# MCU_pinout.net
KiCad netlist of a schematic drawn in Altium Designer
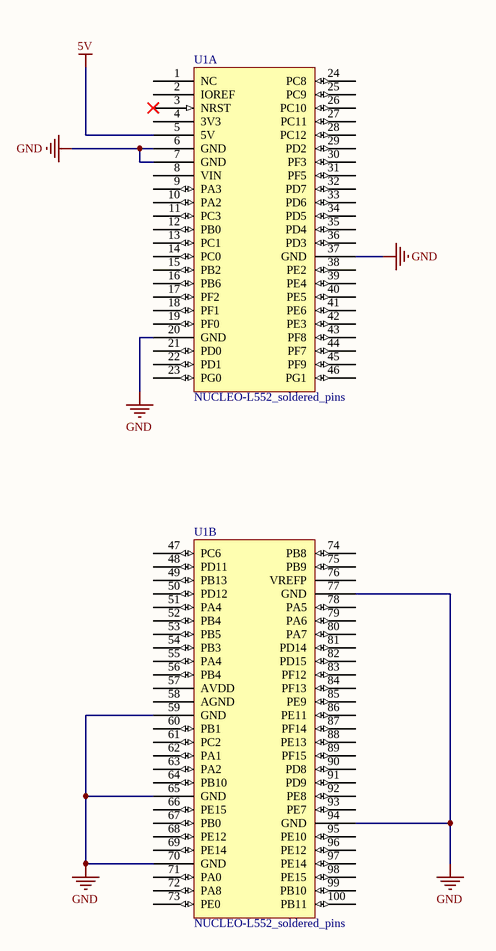
[diagram p0: MCU_pinout.SchDoc]

(export (version "E")
  (design (tool "Eeschema 10.0.6"))
  (components
    (comp (ref "U1")
      (value "NUCLEO-L552_soldered_pins")
      (footprint "FP_NUCLEO-144 inner connector")
      (libsource (lib "hallglib") (part "NUCLEO-L552_inner"))
    )
  )
  (nets
    (net (code "1") (name "5V") (class "Default")
      (node (ref "U1") (pin "5") (pinfunction "5V_5") (pintype "power_in"))
    )
    (net (code "2") (name "GND") (class "Default")
      (node (ref "U1") (pin "20") (pinfunction "GND_20") (pintype "power_in"))
      (node (ref "U1") (pin "37") (pinfunction "GND_37") (pintype "power_in"))
      (node (ref "U1") (pin "59") (pinfunction "GND_59") (pintype "power_in"))
      (node (ref "U1") (pin "6") (pinfunction "GND_6") (pintype "power_in"))
      (node (ref "U1") (pin "65") (pinfunction "GND_65") (pintype "power_in"))
      (node (ref "U1") (pin "7") (pinfunction "GND_7") (pintype "power_in"))
      (node (ref "U1") (pin "70") (pinfunction "GND_70") (pintype "power_in"))
      (node (ref "U1") (pin "77") (pinfunction "GND_77") (pintype "power_in"))
      (node (ref "U1") (pin "94") (pinfunction "GND_94") (pintype "power_in"))
    )
    (net (code "3") (name "unconnected-(U1A-3V3-Pad4)") (class "Default")
      (node (ref "U1") (pin "4") (pinfunction "3V3_4") (pintype "power_in"))
    )
    (net (code "4") (name "unconnected-(U1A-IOREF-Pad2)") (class "Default")
      (node (ref "U1") (pin "2") (pinfunction "IOREF_2") (pintype "power_in"))
    )
    (net (code "5") (name "unconnected-(U1A-NC-Pad1)") (class "Default")
      (node (ref "U1") (pin "1") (pinfunction "NC_1") (pintype "passive"))
    )
    (net (code "6") (name "unconnected-(U1A-NRST-Pad3)") (class "Default")
      (node (ref "U1") (pin "3") (pinfunction "NRST_3") (pintype "input+no_connect"))
    )
    (net (code "7") (name "unconnected-(U1A-PA2-Pad10)") (class "Default")
      (node (ref "U1") (pin "10") (pinfunction "PA2_10") (pintype "bidirectional"))
    )
    (net (code "8") (name "unconnected-(U1A-PA3-Pad9)") (class "Default")
      (node (ref "U1") (pin "9") (pinfunction "PA3_9") (pintype "bidirectional"))
    )
    (net (code "9") (name "unconnected-(U1A-PB0-Pad12)") (class "Default")
      (node (ref "U1") (pin "12") (pinfunction "PB0_12") (pintype "bidirectional"))
    )
    (net (code "10") (name "unconnected-(U1A-PB2-Pad15)") (class "Default")
      (node (ref "U1") (pin "15") (pinfunction "PB2_15") (pintype "bidirectional"))
    )
    (net (code "11") (name "unconnected-(U1A-PB6-Pad16)") (class "Default")
      (node (ref "U1") (pin "16") (pinfunction "PB6_16") (pintype "bidirectional"))
    )
    (net (code "12") (name "unconnected-(U1A-PC0-Pad14)") (class "Default")
      (node (ref "U1") (pin "14") (pinfunction "PC0_14") (pintype "bidirectional"))
    )
    (net (code "13") (name "unconnected-(U1A-PC1-Pad13)") (class "Default")
      (node (ref "U1") (pin "13") (pinfunction "PC1_13") (pintype "bidirectional"))
    )
    (net (code "14") (name "unconnected-(U1A-PC3-Pad11)") (class "Default")
      (node (ref "U1") (pin "11") (pinfunction "PC3_11") (pintype "bidirectional"))
    )
    (net (code "15") (name "unconnected-(U1A-PC8-Pad24)") (class "Default")
      (node (ref "U1") (pin "24") (pinfunction "PC8_24") (pintype "bidirectional"))
    )
    (net (code "16") (name "unconnected-(U1A-PC9-Pad25)") (class "Default")
      (node (ref "U1") (pin "25") (pinfunction "PC9_25") (pintype "bidirectional"))
    )
    (net (code "17") (name "unconnected-(U1A-PC10-Pad26)") (class "Default")
      (node (ref "U1") (pin "26") (pinfunction "PC10_26") (pintype "bidirectional"))
    )
    (net (code "18") (name "unconnected-(U1A-PC11-Pad27)") (class "Default")
      (node (ref "U1") (pin "27") (pinfunction "PC11_27") (pintype "bidirectional"))
    )
    (net (code "19") (name "unconnected-(U1A-PC12-Pad28)") (class "Default")
      (node (ref "U1") (pin "28") (pinfunction "PC12_28") (pintype "bidirectional"))
    )
    (net (code "20") (name "unconnected-(U1A-PD0-Pad21)") (class "Default")
      (node (ref "U1") (pin "21") (pinfunction "PD0_21") (pintype "bidirectional"))
    )
    (net (code "21") (name "unconnected-(U1A-PD1-Pad22)") (class "Default")
      (node (ref "U1") (pin "22") (pinfunction "PD1_22") (pintype "bidirectional"))
    )
    (net (code "22") (name "unconnected-(U1A-PD2-Pad29)") (class "Default")
      (node (ref "U1") (pin "29") (pinfunction "PD2_29") (pintype "bidirectional"))
    )
    (net (code "23") (name "unconnected-(U1A-PD3-Pad36)") (class "Default")
      (node (ref "U1") (pin "36") (pinfunction "PD3_36") (pintype "bidirectional"))
    )
    (net (code "24") (name "unconnected-(U1A-PD4-Pad35)") (class "Default")
      (node (ref "U1") (pin "35") (pinfunction "PD4_35") (pintype "bidirectional"))
    )
    (net (code "25") (name "unconnected-(U1A-PD5-Pad34)") (class "Default")
      (node (ref "U1") (pin "34") (pinfunction "PD5_34") (pintype "bidirectional"))
    )
    (net (code "26") (name "unconnected-(U1A-PD6-Pad33)") (class "Default")
      (node (ref "U1") (pin "33") (pinfunction "PD6_33") (pintype "bidirectional"))
    )
    (net (code "27") (name "unconnected-(U1A-PD7-Pad32)") (class "Default")
      (node (ref "U1") (pin "32") (pinfunction "PD7_32") (pintype "bidirectional"))
    )
    (net (code "28") (name "unconnected-(U1A-PE2-Pad38)") (class "Default")
      (node (ref "U1") (pin "38") (pinfunction "PE2_38") (pintype "bidirectional"))
    )
    (net (code "29") (name "unconnected-(U1A-PE3-Pad42)") (class "Default")
      (node (ref "U1") (pin "42") (pinfunction "PE3_42") (pintype "bidirectional"))
    )
    (net (code "30") (name "unconnected-(U1A-PE4-Pad39)") (class "Default")
      (node (ref "U1") (pin "39") (pinfunction "PE4_39") (pintype "bidirectional"))
    )
    (net (code "31") (name "unconnected-(U1A-PE5-Pad40)") (class "Default")
      (node (ref "U1") (pin "40") (pinfunction "PE5_40") (pintype "bidirectional"))
    )
    (net (code "32") (name "unconnected-(U1A-PE6-Pad41)") (class "Default")
      (node (ref "U1") (pin "41") (pinfunction "PE6_41") (pintype "bidirectional"))
    )
    (net (code "33") (name "unconnected-(U1A-PF0-Pad19)") (class "Default")
      (node (ref "U1") (pin "19") (pinfunction "PF0_19") (pintype "bidirectional"))
    )
    (net (code "34") (name "unconnected-(U1A-PF1-Pad18)") (class "Default")
      (node (ref "U1") (pin "18") (pinfunction "PF1_18") (pintype "bidirectional"))
    )
    (net (code "35") (name "unconnected-(U1A-PF2-Pad17)") (class "Default")
      (node (ref "U1") (pin "17") (pinfunction "PF2_17") (pintype "bidirectional"))
    )
    (net (code "36") (name "unconnected-(U1A-PF3-Pad30)") (class "Default")
      (node (ref "U1") (pin "30") (pinfunction "PF3_30") (pintype "bidirectional"))
    )
    (net (code "37") (name "unconnected-(U1A-PF5-Pad31)") (class "Default")
      (node (ref "U1") (pin "31") (pinfunction "PF5_31") (pintype "bidirectional"))
    )
    (net (code "38") (name "unconnected-(U1A-PF7-Pad44)") (class "Default")
      (node (ref "U1") (pin "44") (pinfunction "PF7_44") (pintype "bidirectional"))
    )
    (net (code "39") (name "unconnected-(U1A-PF8-Pad43)") (class "Default")
      (node (ref "U1") (pin "43") (pinfunction "PF8_43") (pintype "bidirectional"))
    )
    (net (code "40") (name "unconnected-(U1A-PF9-Pad45)") (class "Default")
      (node (ref "U1") (pin "45") (pinfunction "PF9_45") (pintype "bidirectional"))
    )
    (net (code "41") (name "unconnected-(U1A-PG0-Pad23)") (class "Default")
      (node (ref "U1") (pin "23") (pinfunction "PG0_23") (pintype "bidirectional"))
    )
    (net (code "42") (name "unconnected-(U1A-PG1-Pad46)") (class "Default")
      (node (ref "U1") (pin "46") (pinfunction "PG1_46") (pintype "bidirectional"))
    )
    (net (code "43") (name "unconnected-(U1A-VIN-Pad8)") (class "Default")
      (node (ref "U1") (pin "8") (pinfunction "VIN_8") (pintype "power_in"))
    )
    (net (code "44") (name "unconnected-(U1B-AGND-Pad58)") (class "Default")
      (node (ref "U1") (pin "58") (pinfunction "AGND_58") (pintype "power_in"))
    )
    (net (code "45") (name "unconnected-(U1B-AVDD-Pad57)") (class "Default")
      (node (ref "U1") (pin "57") (pinfunction "AVDD_57") (pintype "power_in"))
    )
    (net (code "46") (name "unconnected-(U1B-PA0-Pad71)") (class "Default")
      (node (ref "U1") (pin "71") (pinfunction "PA0_71") (pintype "bidirectional"))
    )
    (net (code "47") (name "unconnected-(U1B-PA1-Pad62)") (class "Default")
      (node (ref "U1") (pin "62") (pinfunction "PA1_62") (pintype "bidirectional"))
    )
    (net (code "48") (name "unconnected-(U1B-PA2-Pad63)") (class "Default")
      (node (ref "U1") (pin "63") (pinfunction "PA2_63") (pintype "bidirectional"))
    )
    (net (code "49") (name "unconnected-(U1B-PA4-Pad51)") (class "Default")
      (node (ref "U1") (pin "51") (pinfunction "PA4_51") (pintype "bidirectional"))
    )
    (net (code "50") (name "unconnected-(U1B-PA4-Pad55)") (class "Default")
      (node (ref "U1") (pin "55") (pinfunction "PA4_55") (pintype "bidirectional"))
    )
    (net (code "51") (name "unconnected-(U1B-PA5-Pad78)") (class "Default")
      (node (ref "U1") (pin "78") (pinfunction "PA5_78") (pintype "bidirectional"))
    )
    (net (code "52") (name "unconnected-(U1B-PA6-Pad79)") (class "Default")
      (node (ref "U1") (pin "79") (pinfunction "PA6_79") (pintype "bidirectional"))
    )
    (net (code "53") (name "unconnected-(U1B-PA7-Pad80)") (class "Default")
      (node (ref "U1") (pin "80") (pinfunction "PA7_80") (pintype "bidirectional"))
    )
    (net (code "54") (name "unconnected-(U1B-PA8-Pad72)") (class "Default")
      (node (ref "U1") (pin "72") (pinfunction "PA8_72") (pintype "bidirectional"))
    )
    (net (code "55") (name "unconnected-(U1B-PB0-Pad67)") (class "Default")
      (node (ref "U1") (pin "67") (pinfunction "PB0_67") (pintype "bidirectional"))
    )
    (net (code "56") (name "unconnected-(U1B-PB1-Pad60)") (class "Default")
      (node (ref "U1") (pin "60") (pinfunction "PB1_60") (pintype "bidirectional"))
    )
    (net (code "57") (name "unconnected-(U1B-PB3-Pad54)") (class "Default")
      (node (ref "U1") (pin "54") (pinfunction "PB3_54") (pintype "bidirectional"))
    )
    (net (code "58") (name "unconnected-(U1B-PB4-Pad52)") (class "Default")
      (node (ref "U1") (pin "52") (pinfunction "PB4_52") (pintype "bidirectional"))
    )
    (net (code "59") (name "unconnected-(U1B-PB4-Pad56)") (class "Default")
      (node (ref "U1") (pin "56") (pinfunction "PB4_56") (pintype "bidirectional"))
    )
    (net (code "60") (name "unconnected-(U1B-PB5-Pad53)") (class "Default")
      (node (ref "U1") (pin "53") (pinfunction "PB5_53") (pintype "bidirectional"))
    )
    (net (code "61") (name "unconnected-(U1B-PB8-Pad74)") (class "Default")
      (node (ref "U1") (pin "74") (pinfunction "PB8_74") (pintype "bidirectional"))
    )
    (net (code "62") (name "unconnected-(U1B-PB9-Pad75)") (class "Default")
      (node (ref "U1") (pin "75") (pinfunction "PB9_75") (pintype "bidirectional"))
    )
    (net (code "63") (name "unconnected-(U1B-PB10-Pad64)") (class "Default")
      (node (ref "U1") (pin "64") (pinfunction "PB10_64") (pintype "bidirectional"))
    )
    (net (code "64") (name "unconnected-(U1B-PB10-Pad99)") (class "Default")
      (node (ref "U1") (pin "99") (pinfunction "PB10_99") (pintype "bidirectional"))
    )
    (net (code "65") (name "unconnected-(U1B-PB11-Pad100)") (class "Default")
      (node (ref "U1") (pin "100") (pinfunction "PB11_100") (pintype "bidirectional"))
    )
    (net (code "66") (name "unconnected-(U1B-PB13-Pad49)") (class "Default")
      (node (ref "U1") (pin "49") (pinfunction "PB13_49") (pintype "bidirectional"))
    )
    (net (code "67") (name "unconnected-(U1B-PC2-Pad61)") (class "Default")
      (node (ref "U1") (pin "61") (pinfunction "PC2_61") (pintype "bidirectional"))
    )
    (net (code "68") (name "unconnected-(U1B-PC6-Pad47)") (class "Default")
      (node (ref "U1") (pin "47") (pinfunction "PC6_47") (pintype "bidirectional"))
    )
    (net (code "69") (name "unconnected-(U1B-PD8-Pad90)") (class "Default")
      (node (ref "U1") (pin "90") (pinfunction "PD8_90") (pintype "bidirectional"))
    )
    (net (code "70") (name "unconnected-(U1B-PD9-Pad91)") (class "Default")
      (node (ref "U1") (pin "91") (pinfunction "PD9_91") (pintype "bidirectional"))
    )
    (net (code "71") (name "unconnected-(U1B-PD11-Pad48)") (class "Default")
      (node (ref "U1") (pin "48") (pinfunction "PD11_48") (pintype "bidirectional"))
    )
    (net (code "72") (name "unconnected-(U1B-PD12-Pad50)") (class "Default")
      (node (ref "U1") (pin "50") (pinfunction "PD12_50") (pintype "bidirectional"))
    )
    (net (code "73") (name "unconnected-(U1B-PD14-Pad81)") (class "Default")
      (node (ref "U1") (pin "81") (pinfunction "PD14_81") (pintype "bidirectional"))
    )
    (net (code "74") (name "unconnected-(U1B-PD15-Pad82)") (class "Default")
      (node (ref "U1") (pin "82") (pinfunction "PD15_82") (pintype "bidirectional"))
    )
    (net (code "75") (name "unconnected-(U1B-PE0-Pad73)") (class "Default")
      (node (ref "U1") (pin "73") (pinfunction "PE0_73") (pintype "bidirectional"))
    )
    (net (code "76") (name "unconnected-(U1B-PE7-Pad93)") (class "Default")
      (node (ref "U1") (pin "93") (pinfunction "PE7_93") (pintype "bidirectional"))
    )
    (net (code "77") (name "unconnected-(U1B-PE8-Pad92)") (class "Default")
      (node (ref "U1") (pin "92") (pinfunction "PE8_92") (pintype "bidirectional"))
    )
    (net (code "78") (name "unconnected-(U1B-PE9-Pad85)") (class "Default")
      (node (ref "U1") (pin "85") (pinfunction "PE9_85") (pintype "bidirectional"))
    )
    (net (code "79") (name "unconnected-(U1B-PE10-Pad95)") (class "Default")
      (node (ref "U1") (pin "95") (pinfunction "PE10_95") (pintype "bidirectional"))
    )
    (net (code "80") (name "unconnected-(U1B-PE11-Pad86)") (class "Default")
      (node (ref "U1") (pin "86") (pinfunction "PE11_86") (pintype "bidirectional"))
    )
    (net (code "81") (name "unconnected-(U1B-PE12-Pad68)") (class "Default")
      (node (ref "U1") (pin "68") (pinfunction "PE12_68") (pintype "bidirectional"))
    )
    (net (code "82") (name "unconnected-(U1B-PE12-Pad96)") (class "Default")
      (node (ref "U1") (pin "96") (pinfunction "PE12_96") (pintype "bidirectional"))
    )
    (net (code "83") (name "unconnected-(U1B-PE13-Pad88)") (class "Default")
      (node (ref "U1") (pin "88") (pinfunction "PE13_88") (pintype "bidirectional"))
    )
    (net (code "84") (name "unconnected-(U1B-PE14-Pad69)") (class "Default")
      (node (ref "U1") (pin "69") (pinfunction "PE14_69") (pintype "bidirectional"))
    )
    (net (code "85") (name "unconnected-(U1B-PE14-Pad97)") (class "Default")
      (node (ref "U1") (pin "97") (pinfunction "PE14_97") (pintype "bidirectional"))
    )
    (net (code "86") (name "unconnected-(U1B-PE15-Pad66)") (class "Default")
      (node (ref "U1") (pin "66") (pinfunction "PE15_66") (pintype "bidirectional"))
    )
    (net (code "87") (name "unconnected-(U1B-PE15-Pad98)") (class "Default")
      (node (ref "U1") (pin "98") (pinfunction "PE15_98") (pintype "bidirectional"))
    )
    (net (code "88") (name "unconnected-(U1B-PF12-Pad83)") (class "Default")
      (node (ref "U1") (pin "83") (pinfunction "PF12_83") (pintype "bidirectional"))
    )
    (net (code "89") (name "unconnected-(U1B-PF13-Pad84)") (class "Default")
      (node (ref "U1") (pin "84") (pinfunction "PF13_84") (pintype "bidirectional"))
    )
    (net (code "90") (name "unconnected-(U1B-PF14-Pad87)") (class "Default")
      (node (ref "U1") (pin "87") (pinfunction "PF14_87") (pintype "bidirectional"))
    )
    (net (code "91") (name "unconnected-(U1B-PF15-Pad89)") (class "Default")
      (node (ref "U1") (pin "89") (pinfunction "PF15_89") (pintype "bidirectional"))
    )
    (net (code "92") (name "unconnected-(U1B-VREFP-Pad76)") (class "Default")
      (node (ref "U1") (pin "76") (pinfunction "VREFP_76") (pintype "power_in"))
    )
  )
)
